# LED.net
KiCad netlist of a schematic drawn in Altium Designer
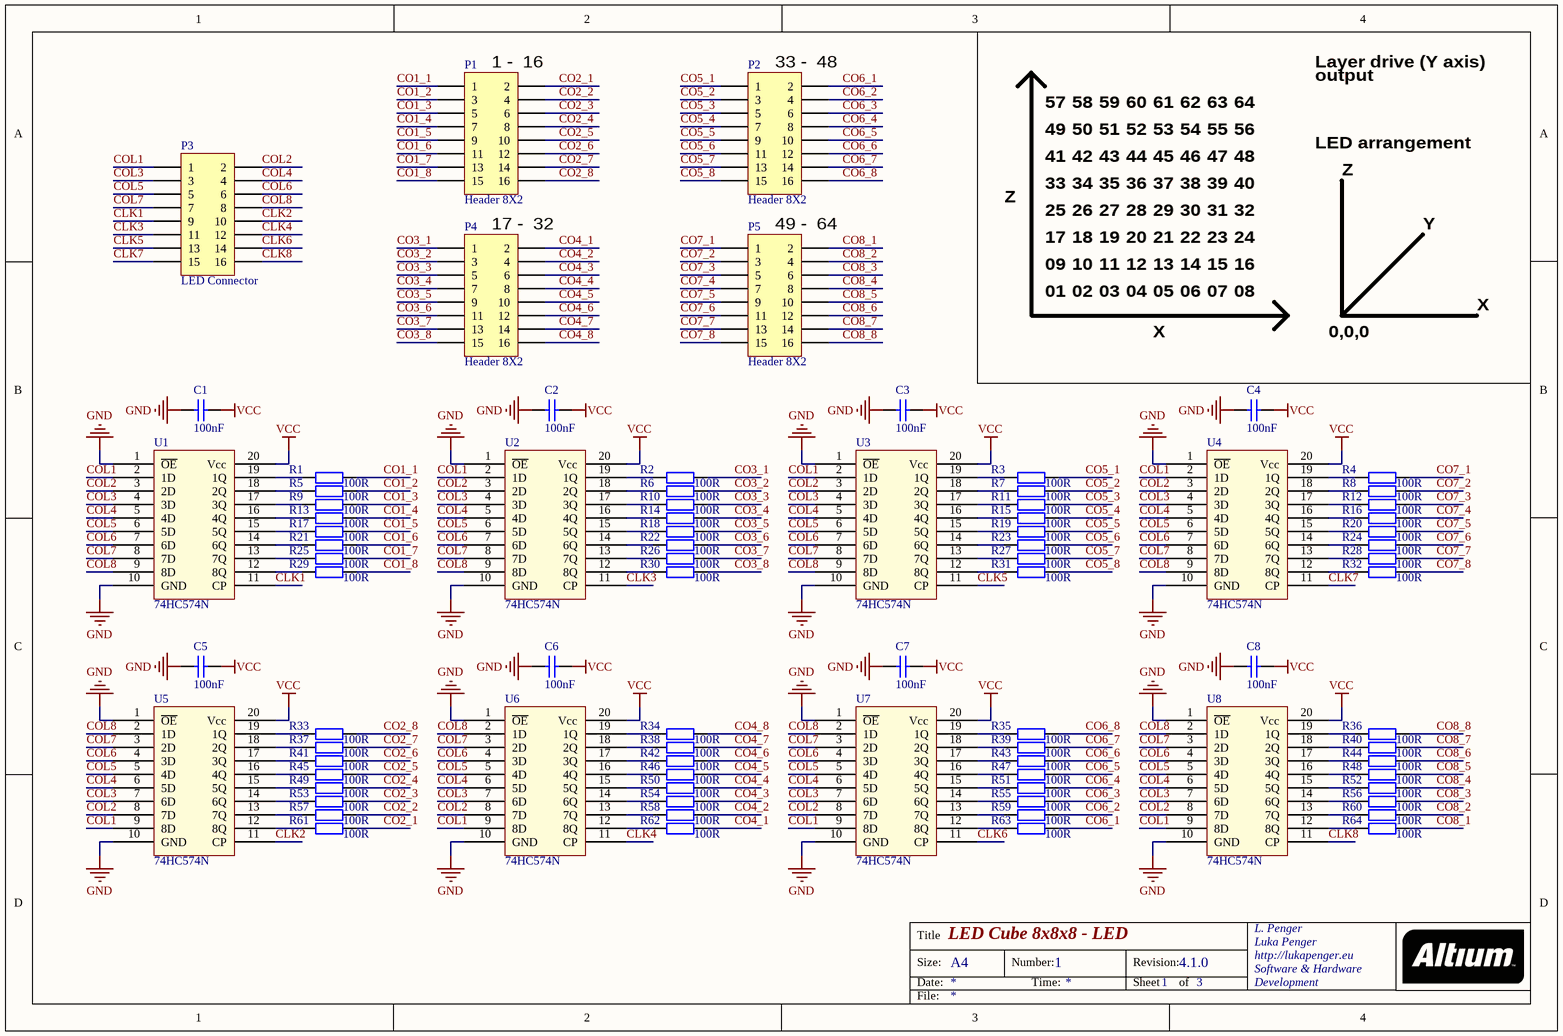
[diagram p0: LED.SchDoc]

(export (version "E")
  (design (tool "Eeschema 10.0.6"))
  (components
    (comp (ref "C1")
      (value "100nF")
      (footprint "1608[0603]")
      (description "Capacitor")
      (fields (field (name "PUBLISHER") "Altium Limited"))
      (libsource (lib "Miscellaneous Devices") (part "Cap"))
    )
    (comp (ref "C2")
      (value "100nF")
      (footprint "1608[0603]")
      (description "Capacitor")
      (fields (field (name "PUBLISHER") "Altium Limited"))
      (libsource (lib "Miscellaneous Devices") (part "Cap"))
    )
    (comp (ref "C3")
      (value "100nF")
      (footprint "1608[0603]")
      (description "Capacitor")
      (fields (field (name "PUBLISHER") "Altium Limited"))
      (libsource (lib "Miscellaneous Devices") (part "Cap"))
    )
    (comp (ref "C4")
      (value "100nF")
      (footprint "1608[0603]")
      (description "Capacitor")
      (fields (field (name "PUBLISHER") "Altium Limited"))
      (libsource (lib "Miscellaneous Devices") (part "Cap"))
    )
    (comp (ref "C5")
      (value "100nF")
      (footprint "1608[0603]")
      (description "Capacitor")
      (fields (field (name "PUBLISHER") "Altium Limited"))
      (libsource (lib "Miscellaneous Devices") (part "Cap"))
    )
    (comp (ref "C6")
      (value "100nF")
      (footprint "1608[0603]")
      (description "Capacitor")
      (fields (field (name "PUBLISHER") "Altium Limited"))
      (libsource (lib "Miscellaneous Devices") (part "Cap"))
    )
    (comp (ref "C7")
      (value "100nF")
      (footprint "1608[0603]")
      (description "Capacitor")
      (fields (field (name "PUBLISHER") "Altium Limited"))
      (libsource (lib "Miscellaneous Devices") (part "Cap"))
    )
    (comp (ref "C8")
      (value "100nF")
      (footprint "1608[0603]")
      (description "Capacitor")
      (fields (field (name "PUBLISHER") "Altium Limited"))
      (libsource (lib "Miscellaneous Devices") (part "Cap"))
    )
    (comp (ref "P1")
      (value "Header 8X2")
      (footprint "IDC-2x8")
      (description "Header, 8-Pin, Dual row")
      (fields (field (name "PUBLISHER") "Altium Limited"))
      (libsource (lib "Miscellaneous Connectors") (part "Header 8X2"))
    )
    (comp (ref "P2")
      (value "Header 8X2")
      (footprint "IDC-2x8")
      (description "Header, 8-Pin, Dual row")
      (fields (field (name "PUBLISHER") "Altium Limited"))
      (libsource (lib "Miscellaneous Connectors") (part "Header 8X2"))
    )
    (comp (ref "P3")
      (value "LED Connector")
      (footprint "IDC-2x8")
      (description "Header, 8-Pin, Dual row")
      (fields (field (name "PUBLISHER") "Altium Limited"))
      (libsource (lib "Miscellaneous Connectors") (part "Header 8X2"))
    )
    (comp (ref "P4")
      (value "Header 8X2")
      (footprint "IDC-2x8")
      (description "Header, 8-Pin, Dual row")
      (fields (field (name "PUBLISHER") "Altium Limited"))
      (libsource (lib "Miscellaneous Connectors") (part "Header 8X2"))
    )
    (comp (ref "P5")
      (value "Header 8X2")
      (footprint "IDC-2x8")
      (description "Header, 8-Pin, Dual row")
      (fields (field (name "PUBLISHER") "Altium Limited"))
      (libsource (lib "Miscellaneous Connectors") (part "Header 8X2"))
    )
    (comp (ref "R1")
      (value "100R")
      (footprint "C1206")
      (description "Resistor")
      (fields (field (name "PUBLISHER") "Altium Limited"))
      (libsource (lib "Miscellaneous Devices") (part "Res2"))
    )
    (comp (ref "R2")
      (value "100R")
      (footprint "C1206")
      (description "Resistor")
      (fields (field (name "PUBLISHER") "Altium Limited"))
      (libsource (lib "Miscellaneous Devices") (part "Res2"))
    )
    (comp (ref "R3")
      (value "100R")
      (footprint "C1206")
      (description "Resistor")
      (fields (field (name "PUBLISHER") "Altium Limited"))
      (libsource (lib "Miscellaneous Devices") (part "Res2"))
    )
    (comp (ref "R4")
      (value "100R")
      (footprint "C1206")
      (description "Resistor")
      (fields (field (name "PUBLISHER") "Altium Limited"))
      (libsource (lib "Miscellaneous Devices") (part "Res2"))
    )
    (comp (ref "R5")
      (value "100R")
      (footprint "C1206")
      (description "Resistor")
      (fields (field (name "PUBLISHER") "Altium Limited"))
      (libsource (lib "Miscellaneous Devices") (part "Res2"))
    )
    (comp (ref "R6")
      (value "100R")
      (footprint "C1206")
      (description "Resistor")
      (fields (field (name "PUBLISHER") "Altium Limited"))
      (libsource (lib "Miscellaneous Devices") (part "Res2"))
    )
    (comp (ref "R7")
      (value "100R")
      (footprint "C1206")
      (description "Resistor")
      (fields (field (name "PUBLISHER") "Altium Limited"))
      (libsource (lib "Miscellaneous Devices") (part "Res2"))
    )
    (comp (ref "R8")
      (value "100R")
      (footprint "C1206")
      (description "Resistor")
      (fields (field (name "PUBLISHER") "Altium Limited"))
      (libsource (lib "Miscellaneous Devices") (part "Res2"))
    )
    (comp (ref "R9")
      (value "100R")
      (footprint "C1206")
      (description "Resistor")
      (fields (field (name "PUBLISHER") "Altium Limited"))
      (libsource (lib "Miscellaneous Devices") (part "Res2"))
    )
    (comp (ref "R10")
      (value "100R")
      (footprint "C1206")
      (description "Resistor")
      (fields (field (name "PUBLISHER") "Altium Limited"))
      (libsource (lib "Miscellaneous Devices") (part "Res2"))
    )
    (comp (ref "R11")
      (value "100R")
      (footprint "C1206")
      (description "Resistor")
      (fields (field (name "PUBLISHER") "Altium Limited"))
      (libsource (lib "Miscellaneous Devices") (part "Res2"))
    )
    (comp (ref "R12")
      (value "100R")
      (footprint "C1206")
      (description "Resistor")
      (fields (field (name "PUBLISHER") "Altium Limited"))
      (libsource (lib "Miscellaneous Devices") (part "Res2"))
    )
    (comp (ref "R13")
      (value "100R")
      (footprint "C1206")
      (description "Resistor")
      (fields (field (name "PUBLISHER") "Altium Limited"))
      (libsource (lib "Miscellaneous Devices") (part "Res2"))
    )
    (comp (ref "R14")
      (value "100R")
      (footprint "C1206")
      (description "Resistor")
      (fields (field (name "PUBLISHER") "Altium Limited"))
      (libsource (lib "Miscellaneous Devices") (part "Res2"))
    )
    (comp (ref "R15")
      (value "100R")
      (footprint "C1206")
      (description "Resistor")
      (fields (field (name "PUBLISHER") "Altium Limited"))
      (libsource (lib "Miscellaneous Devices") (part "Res2"))
    )
    (comp (ref "R16")
      (value "100R")
      (footprint "C1206")
      (description "Resistor")
      (fields (field (name "PUBLISHER") "Altium Limited"))
      (libsource (lib "Miscellaneous Devices") (part "Res2"))
    )
    (comp (ref "R17")
      (value "100R")
      (footprint "C1206")
      (description "Resistor")
      (fields (field (name "PUBLISHER") "Altium Limited"))
      (libsource (lib "Miscellaneous Devices") (part "Res2"))
    )
    (comp (ref "R18")
      (value "100R")
      (footprint "C1206")
      (description "Resistor")
      (fields (field (name "PUBLISHER") "Altium Limited"))
      (libsource (lib "Miscellaneous Devices") (part "Res2"))
    )
    (comp (ref "R19")
      (value "100R")
      (footprint "C1206")
      (description "Resistor")
      (fields (field (name "PUBLISHER") "Altium Limited"))
      (libsource (lib "Miscellaneous Devices") (part "Res2"))
    )
    (comp (ref "R20")
      (value "100R")
      (footprint "C1206")
      (description "Resistor")
      (fields (field (name "PUBLISHER") "Altium Limited"))
      (libsource (lib "Miscellaneous Devices") (part "Res2"))
    )
    (comp (ref "R21")
      (value "100R")
      (footprint "C1206")
      (description "Resistor")
      (fields (field (name "PUBLISHER") "Altium Limited"))
      (libsource (lib "Miscellaneous Devices") (part "Res2"))
    )
    (comp (ref "R22")
      (value "100R")
      (footprint "C1206")
      (description "Resistor")
      (fields (field (name "PUBLISHER") "Altium Limited"))
      (libsource (lib "Miscellaneous Devices") (part "Res2"))
    )
    (comp (ref "R23")
      (value "100R")
      (footprint "C1206")
      (description "Resistor")
      (fields (field (name "PUBLISHER") "Altium Limited"))
      (libsource (lib "Miscellaneous Devices") (part "Res2"))
    )
    (comp (ref "R24")
      (value "100R")
      (footprint "C1206")
      (description "Resistor")
      (fields (field (name "PUBLISHER") "Altium Limited"))
      (libsource (lib "Miscellaneous Devices") (part "Res2"))
    )
    (comp (ref "R25")
      (value "100R")
      (footprint "C1206")
      (description "Resistor")
      (fields (field (name "PUBLISHER") "Altium Limited"))
      (libsource (lib "Miscellaneous Devices") (part "Res2"))
    )
    (comp (ref "R26")
      (value "100R")
      (footprint "C1206")
      (description "Resistor")
      (fields (field (name "PUBLISHER") "Altium Limited"))
      (libsource (lib "Miscellaneous Devices") (part "Res2"))
    )
    (comp (ref "R27")
      (value "100R")
      (footprint "C1206")
      (description "Resistor")
      (fields (field (name "PUBLISHER") "Altium Limited"))
      (libsource (lib "Miscellaneous Devices") (part "Res2"))
    )
    (comp (ref "R28")
      (value "100R")
      (footprint "C1206")
      (description "Resistor")
      (fields (field (name "PUBLISHER") "Altium Limited"))
      (libsource (lib "Miscellaneous Devices") (part "Res2"))
    )
    (comp (ref "R29")
      (value "100R")
      (footprint "C1206")
      (description "Resistor")
      (fields (field (name "PUBLISHER") "Altium Limited"))
      (libsource (lib "Miscellaneous Devices") (part "Res2"))
    )
    (comp (ref "R30")
      (value "100R")
      (footprint "C1206")
      (description "Resistor")
      (fields (field (name "PUBLISHER") "Altium Limited"))
      (libsource (lib "Miscellaneous Devices") (part "Res2"))
    )
    (comp (ref "R31")
      (value "100R")
      (footprint "C1206")
      (description "Resistor")
      (fields (field (name "PUBLISHER") "Altium Limited"))
      (libsource (lib "Miscellaneous Devices") (part "Res2"))
    )
    (comp (ref "R32")
      (value "100R")
      (footprint "C1206")
      (description "Resistor")
      (fields (field (name "PUBLISHER") "Altium Limited"))
      (libsource (lib "Miscellaneous Devices") (part "Res2"))
    )
    (comp (ref "R33")
      (value "100R")
      (footprint "C1206")
      (description "Resistor")
      (fields (field (name "PUBLISHER") "Altium Limited"))
      (libsource (lib "Miscellaneous Devices") (part "Res2"))
    )
    (comp (ref "R34")
      (value "100R")
      (footprint "C1206")
      (description "Resistor")
      (fields (field (name "PUBLISHER") "Altium Limited"))
      (libsource (lib "Miscellaneous Devices") (part "Res2"))
    )
    (comp (ref "R35")
      (value "100R")
      (footprint "C1206")
      (description "Resistor")
      (fields (field (name "PUBLISHER") "Altium Limited"))
      (libsource (lib "Miscellaneous Devices") (part "Res2"))
    )
    (comp (ref "R36")
      (value "100R")
      (footprint "C1206")
      (description "Resistor")
      (fields (field (name "PUBLISHER") "Altium Limited"))
      (libsource (lib "Miscellaneous Devices") (part "Res2"))
    )
    (comp (ref "R37")
      (value "100R")
      (footprint "C1206")
      (description "Resistor")
      (fields (field (name "PUBLISHER") "Altium Limited"))
      (libsource (lib "Miscellaneous Devices") (part "Res2"))
    )
    (comp (ref "R38")
      (value "100R")
      (footprint "C1206")
      (description "Resistor")
      (fields (field (name "PUBLISHER") "Altium Limited"))
      (libsource (lib "Miscellaneous Devices") (part "Res2"))
    )
    (comp (ref "R39")
      (value "100R")
      (footprint "C1206")
      (description "Resistor")
      (fields (field (name "PUBLISHER") "Altium Limited"))
      (libsource (lib "Miscellaneous Devices") (part "Res2"))
    )
    (comp (ref "R40")
      (value "100R")
      (footprint "C1206")
      (description "Resistor")
      (fields (field (name "PUBLISHER") "Altium Limited"))
      (libsource (lib "Miscellaneous Devices") (part "Res2"))
    )
    (comp (ref "R41")
      (value "100R")
      (footprint "C1206")
      (description "Resistor")
      (fields (field (name "PUBLISHER") "Altium Limited"))
      (libsource (lib "Miscellaneous Devices") (part "Res2"))
    )
    (comp (ref "R42")
      (value "100R")
      (footprint "C1206")
      (description "Resistor")
      (fields (field (name "PUBLISHER") "Altium Limited"))
      (libsource (lib "Miscellaneous Devices") (part "Res2"))
    )
    (comp (ref "R43")
      (value "100R")
      (footprint "C1206")
      (description "Resistor")
      (fields (field (name "PUBLISHER") "Altium Limited"))
      (libsource (lib "Miscellaneous Devices") (part "Res2"))
    )
    (comp (ref "R44")
      (value "100R")
      (footprint "C1206")
      (description "Resistor")
      (fields (field (name "PUBLISHER") "Altium Limited"))
      (libsource (lib "Miscellaneous Devices") (part "Res2"))
    )
    (comp (ref "R45")
      (value "100R")
      (footprint "C1206")
      (description "Resistor")
      (fields (field (name "PUBLISHER") "Altium Limited"))
      (libsource (lib "Miscellaneous Devices") (part "Res2"))
    )
    (comp (ref "R46")
      (value "100R")
      (footprint "C1206")
      (description "Resistor")
      (fields (field (name "PUBLISHER") "Altium Limited"))
      (libsource (lib "Miscellaneous Devices") (part "Res2"))
    )
    (comp (ref "R47")
      (value "100R")
      (footprint "C1206")
      (description "Resistor")
      (fields (field (name "PUBLISHER") "Altium Limited"))
      (libsource (lib "Miscellaneous Devices") (part "Res2"))
    )
    (comp (ref "R48")
      (value "100R")
      (footprint "C1206")
      (description "Resistor")
      (fields (field (name "PUBLISHER") "Altium Limited"))
      (libsource (lib "Miscellaneous Devices") (part "Res2"))
    )
    (comp (ref "R49")
      (value "100R")
      (footprint "C1206")
      (description "Resistor")
      (fields (field (name "PUBLISHER") "Altium Limited"))
      (libsource (lib "Miscellaneous Devices") (part "Res2"))
    )
    (comp (ref "R50")
      (value "100R")
      (footprint "C1206")
      (description "Resistor")
      (fields (field (name "PUBLISHER") "Altium Limited"))
      (libsource (lib "Miscellaneous Devices") (part "Res2"))
    )
    (comp (ref "R51")
      (value "100R")
      (footprint "C1206")
      (description "Resistor")
      (fields (field (name "PUBLISHER") "Altium Limited"))
      (libsource (lib "Miscellaneous Devices") (part "Res2"))
    )
    (comp (ref "R52")
      (value "100R")
      (footprint "C1206")
      (description "Resistor")
      (fields (field (name "PUBLISHER") "Altium Limited"))
      (libsource (lib "Miscellaneous Devices") (part "Res2"))
    )
    (comp (ref "R53")
      (value "100R")
      (footprint "C1206")
      (description "Resistor")
      (fields (field (name "PUBLISHER") "Altium Limited"))
      (libsource (lib "Miscellaneous Devices") (part "Res2"))
    )
    (comp (ref "R54")
      (value "100R")
      (footprint "C1206")
      (description "Resistor")
      (fields (field (name "PUBLISHER") "Altium Limited"))
      (libsource (lib "Miscellaneous Devices") (part "Res2"))
    )
    (comp (ref "R55")
      (value "100R")
      (footprint "C1206")
      (description "Resistor")
      (fields (field (name "PUBLISHER") "Altium Limited"))
      (libsource (lib "Miscellaneous Devices") (part "Res2"))
    )
    (comp (ref "R56")
      (value "100R")
      (footprint "C1206")
      (description "Resistor")
      (fields (field (name "PUBLISHER") "Altium Limited"))
      (libsource (lib "Miscellaneous Devices") (part "Res2"))
    )
    (comp (ref "R57")
      (value "100R")
      (footprint "C1206")
      (description "Resistor")
      (fields (field (name "PUBLISHER") "Altium Limited"))
      (libsource (lib "Miscellaneous Devices") (part "Res2"))
    )
    (comp (ref "R58")
      (value "100R")
      (footprint "C1206")
      (description "Resistor")
      (fields (field (name "PUBLISHER") "Altium Limited"))
      (libsource (lib "Miscellaneous Devices") (part "Res2"))
    )
    (comp (ref "R59")
      (value "100R")
      (footprint "C1206")
      (description "Resistor")
      (fields (field (name "PUBLISHER") "Altium Limited"))
      (libsource (lib "Miscellaneous Devices") (part "Res2"))
    )
    (comp (ref "R60")
      (value "100R")
      (footprint "C1206")
      (description "Resistor")
      (fields (field (name "PUBLISHER") "Altium Limited"))
      (libsource (lib "Miscellaneous Devices") (part "Res2"))
    )
    (comp (ref "R61")
      (value "100R")
      (footprint "C1206")
      (description "Resistor")
      (fields (field (name "PUBLISHER") "Altium Limited"))
      (libsource (lib "Miscellaneous Devices") (part "Res2"))
    )
    (comp (ref "R62")
      (value "100R")
      (footprint "C1206")
      (description "Resistor")
      (fields (field (name "PUBLISHER") "Altium Limited"))
      (libsource (lib "Miscellaneous Devices") (part "Res2"))
    )
    (comp (ref "R63")
      (value "100R")
      (footprint "C1206")
      (description "Resistor")
      (fields (field (name "PUBLISHER") "Altium Limited"))
      (libsource (lib "Miscellaneous Devices") (part "Res2"))
    )
    (comp (ref "R64")
      (value "100R")
      (footprint "C1206")
      (description "Resistor")
      (fields (field (name "PUBLISHER") "Altium Limited"))
      (libsource (lib "Miscellaneous Devices") (part "Res2"))
    )
    (comp (ref "U1")
      (value "74HC574N")
      (footprint "DIP20")
      (description "D Flip Flops")
      (libsource (lib "LukaLIBRARY") (part "74HCT574"))
    )
    (comp (ref "U2")
      (value "74HC574N")
      (footprint "DIP20")
      (description "D Flip Flops")
      (libsource (lib "LukaLIBRARY") (part "74HCT574"))
    )
    (comp (ref "U3")
      (value "74HC574N")
      (footprint "DIP20")
      (description "D Flip Flops")
      (libsource (lib "LukaLIBRARY") (part "74HCT574"))
    )
    (comp (ref "U4")
      (value "74HC574N")
      (footprint "DIP20")
      (description "D Flip Flops")
      (libsource (lib "LukaLIBRARY") (part "74HCT574"))
    )
    (comp (ref "U5")
      (value "74HC574N")
      (footprint "DIP20")
      (description "D Flip Flops")
      (libsource (lib "LukaLIBRARY") (part "74HCT574"))
    )
    (comp (ref "U6")
      (value "74HC574N")
      (footprint "DIP20")
      (description "D Flip Flops")
      (libsource (lib "LukaLIBRARY") (part "74HCT574"))
    )
    (comp (ref "U7")
      (value "74HC574N")
      (footprint "DIP20")
      (description "D Flip Flops")
      (libsource (lib "LukaLIBRARY") (part "74HCT574"))
    )
    (comp (ref "U8")
      (value "74HC574N")
      (footprint "DIP20")
      (description "D Flip Flops")
      (libsource (lib "LukaLIBRARY") (part "74HCT574"))
    )
  )
  (nets
    (net (code "1") (name "/CLK1") (class "Default")
      (node (ref "P3") (pin "9") (pinfunction "9_9") (pintype "passive"))
      (node (ref "U1") (pin "11") (pinfunction "CP_11") (pintype "passive"))
    )
    (net (code "2") (name "/CLK2") (class "Default")
      (node (ref "P3") (pin "10") (pinfunction "10_10") (pintype "passive"))
      (node (ref "U5") (pin "11") (pinfunction "CP_11") (pintype "passive"))
    )
    (net (code "3") (name "/CLK3") (class "Default")
      (node (ref "P3") (pin "11") (pinfunction "11_11") (pintype "passive"))
      (node (ref "U2") (pin "11") (pinfunction "CP_11") (pintype "passive"))
    )
    (net (code "4") (name "/CLK4") (class "Default")
      (node (ref "P3") (pin "12") (pinfunction "12_12") (pintype "passive"))
      (node (ref "U6") (pin "11") (pinfunction "CP_11") (pintype "passive"))
    )
    (net (code "5") (name "/CLK5") (class "Default")
      (node (ref "P3") (pin "13") (pinfunction "13_13") (pintype "passive"))
      (node (ref "U3") (pin "11") (pinfunction "CP_11") (pintype "passive"))
    )
    (net (code "6") (name "/CLK6") (class "Default")
      (node (ref "P3") (pin "14") (pinfunction "14_14") (pintype "passive"))
      (node (ref "U7") (pin "11") (pinfunction "CP_11") (pintype "passive"))
    )
    (net (code "7") (name "/CLK7") (class "Default")
      (node (ref "P3") (pin "15") (pinfunction "15_15") (pintype "passive"))
      (node (ref "U4") (pin "11") (pinfunction "CP_11") (pintype "passive"))
    )
    (net (code "8") (name "/CLK8") (class "Default")
      (node (ref "P3") (pin "16") (pinfunction "16_16") (pintype "passive"))
      (node (ref "U8") (pin "11") (pinfunction "CP_11") (pintype "passive"))
    )
    (net (code "9") (name "/CO1_1") (class "Default")
      (node (ref "P1") (pin "1") (pinfunction "1_1") (pintype "passive"))
      (node (ref "R1") (pin "2") (pinfunction "2_2") (pintype "passive"))
    )
    (net (code "10") (name "/CO1_2") (class "Default")
      (node (ref "P1") (pin "3") (pinfunction "3_3") (pintype "passive"))
      (node (ref "R5") (pin "2") (pinfunction "2_2") (pintype "passive"))
    )
    (net (code "11") (name "/CO1_3") (class "Default")
      (node (ref "P1") (pin "5") (pinfunction "5_5") (pintype "passive"))
      (node (ref "R9") (pin "2") (pinfunction "2_2") (pintype "passive"))
    )
    (net (code "12") (name "/CO1_4") (class "Default")
      (node (ref "P1") (pin "7") (pinfunction "7_7") (pintype "passive"))
      (node (ref "R13") (pin "2") (pinfunction "2_2") (pintype "passive"))
    )
    (net (code "13") (name "/CO1_5") (class "Default")
      (node (ref "P1") (pin "9") (pinfunction "9_9") (pintype "passive"))
      (node (ref "R17") (pin "2") (pinfunction "2_2") (pintype "passive"))
    )
    (net (code "14") (name "/CO1_6") (class "Default")
      (node (ref "P1") (pin "11") (pinfunction "11_11") (pintype "passive"))
      (node (ref "R21") (pin "2") (pinfunction "2_2") (pintype "passive"))
    )
    (net (code "15") (name "/CO1_7") (class "Default")
      (node (ref "P1") (pin "13") (pinfunction "13_13") (pintype "passive"))
      (node (ref "R25") (pin "2") (pinfunction "2_2") (pintype "passive"))
    )
    (net (code "16") (name "/CO1_8") (class "Default")
      (node (ref "P1") (pin "15") (pinfunction "15_15") (pintype "passive"))
      (node (ref "R29") (pin "2") (pinfunction "2_2") (pintype "passive"))
    )
    (net (code "17") (name "/CO2_1") (class "Default")
      (node (ref "P1") (pin "2") (pinfunction "2_2") (pintype "passive"))
      (node (ref "R61") (pin "2") (pinfunction "2_2") (pintype "passive"))
    )
    (net (code "18") (name "/CO2_2") (class "Default")
      (node (ref "P1") (pin "4") (pinfunction "4_4") (pintype "passive"))
      (node (ref "R57") (pin "2") (pinfunction "2_2") (pintype "passive"))
    )
    (net (code "19") (name "/CO2_3") (class "Default")
      (node (ref "P1") (pin "6") (pinfunction "6_6") (pintype "passive"))
      (node (ref "R53") (pin "2") (pinfunction "2_2") (pintype "passive"))
    )
    (net (code "20") (name "/CO2_4") (class "Default")
      (node (ref "P1") (pin "8") (pinfunction "8_8") (pintype "passive"))
      (node (ref "R49") (pin "2") (pinfunction "2_2") (pintype "passive"))
    )
    (net (code "21") (name "/CO2_5") (class "Default")
      (node (ref "P1") (pin "10") (pinfunction "10_10") (pintype "passive"))
      (node (ref "R45") (pin "2") (pinfunction "2_2") (pintype "passive"))
    )
    (net (code "22") (name "/CO2_6") (class "Default")
      (node (ref "P1") (pin "12") (pinfunction "12_12") (pintype "passive"))
      (node (ref "R41") (pin "2") (pinfunction "2_2") (pintype "passive"))
    )
    (net (code "23") (name "/CO2_7") (class "Default")
      (node (ref "P1") (pin "14") (pinfunction "14_14") (pintype "passive"))
      (node (ref "R37") (pin "2") (pinfunction "2_2") (pintype "passive"))
    )
    (net (code "24") (name "/CO2_8") (class "Default")
      (node (ref "P1") (pin "16") (pinfunction "16_16") (pintype "passive"))
      (node (ref "R33") (pin "2") (pinfunction "2_2") (pintype "passive"))
    )
    (net (code "25") (name "/CO3_1") (class "Default")
      (node (ref "P4") (pin "1") (pinfunction "1_1") (pintype "passive"))
      (node (ref "R2") (pin "2") (pinfunction "2_2") (pintype "passive"))
    )
    (net (code "26") (name "/CO3_2") (class "Default")
      (node (ref "P4") (pin "3") (pinfunction "3_3") (pintype "passive"))
      (node (ref "R6") (pin "2") (pinfunction "2_2") (pintype "passive"))
    )
    (net (code "27") (name "/CO3_3") (class "Default")
      (node (ref "P4") (pin "5") (pinfunction "5_5") (pintype "passive"))
      (node (ref "R10") (pin "2") (pinfunction "2_2") (pintype "passive"))
    )
    (net (code "28") (name "/CO3_4") (class "Default")
      (node (ref "P4") (pin "7") (pinfunction "7_7") (pintype "passive"))
      (node (ref "R14") (pin "2") (pinfunction "2_2") (pintype "passive"))
    )
    (net (code "29") (name "/CO3_5") (class "Default")
      (node (ref "P4") (pin "9") (pinfunction "9_9") (pintype "passive"))
      (node (ref "R18") (pin "2") (pinfunction "2_2") (pintype "passive"))
    )
    (net (code "30") (name "/CO3_6") (class "Default")
      (node (ref "P4") (pin "11") (pinfunction "11_11") (pintype "passive"))
      (node (ref "R22") (pin "2") (pinfunction "2_2") (pintype "passive"))
    )
    (net (code "31") (name "/CO3_7") (class "Default")
      (node (ref "P4") (pin "13") (pinfunction "13_13") (pintype "passive"))
      (node (ref "R26") (pin "2") (pinfunction "2_2") (pintype "passive"))
    )
    (net (code "32") (name "/CO3_8") (class "Default")
      (node (ref "P4") (pin "15") (pinfunction "15_15") (pintype "passive"))
      (node (ref "R30") (pin "2") (pinfunction "2_2") (pintype "passive"))
    )
    (net (code "33") (name "/CO4_1") (class "Default")
      (node (ref "P4") (pin "2") (pinfunction "2_2") (pintype "passive"))
      (node (ref "R62") (pin "2") (pinfunction "2_2") (pintype "passive"))
    )
    (net (code "34") (name "/CO4_2") (class "Default")
      (node (ref "P4") (pin "4") (pinfunction "4_4") (pintype "passive"))
      (node (ref "R58") (pin "2") (pinfunction "2_2") (pintype "passive"))
    )
    (net (code "35") (name "/CO4_3") (class "Default")
      (node (ref "P4") (pin "6") (pinfunction "6_6") (pintype "passive"))
      (node (ref "R54") (pin "2") (pinfunction "2_2") (pintype "passive"))
    )
    (net (code "36") (name "/CO4_4") (class "Default")
      (node (ref "P4") (pin "8") (pinfunction "8_8") (pintype "passive"))
      (node (ref "R50") (pin "2") (pinfunction "2_2") (pintype "passive"))
    )
    (net (code "37") (name "/CO4_5") (class "Default")
      (node (ref "P4") (pin "10") (pinfunction "10_10") (pintype "passive"))
      (node (ref "R46") (pin "2") (pinfunction "2_2") (pintype "passive"))
    )
    (net (code "38") (name "/CO4_6") (class "Default")
      (node (ref "P4") (pin "12") (pinfunction "12_12") (pintype "passive"))
      (node (ref "R42") (pin "2") (pinfunction "2_2") (pintype "passive"))
    )
    (net (code "39") (name "/CO4_7") (class "Default")
      (node (ref "P4") (pin "14") (pinfunction "14_14") (pintype "passive"))
      (node (ref "R38") (pin "2") (pinfunction "2_2") (pintype "passive"))
    )
    (net (code "40") (name "/CO4_8") (class "Default")
      (node (ref "P4") (pin "16") (pinfunction "16_16") (pintype "passive"))
      (node (ref "R34") (pin "2") (pinfunction "2_2") (pintype "passive"))
    )
    (net (code "41") (name "/CO5_1") (class "Default")
      (node (ref "P2") (pin "1") (pinfunction "1_1") (pintype "passive"))
      (node (ref "R3") (pin "2") (pinfunction "2_2") (pintype "passive"))
    )
    (net (code "42") (name "/CO5_2") (class "Default")
      (node (ref "P2") (pin "3") (pinfunction "3_3") (pintype "passive"))
      (node (ref "R7") (pin "2") (pinfunction "2_2") (pintype "passive"))
    )
    (net (code "43") (name "/CO5_3") (class "Default")
      (node (ref "P2") (pin "5") (pinfunction "5_5") (pintype "passive"))
      (node (ref "R11") (pin "2") (pinfunction "2_2") (pintype "passive"))
    )
    (net (code "44") (name "/CO5_4") (class "Default")
      (node (ref "P2") (pin "7") (pinfunction "7_7") (pintype "passive"))
      (node (ref "R15") (pin "2") (pinfunction "2_2") (pintype "passive"))
    )
    (net (code "45") (name "/CO5_5") (class "Default")
      (node (ref "P2") (pin "9") (pinfunction "9_9") (pintype "passive"))
      (node (ref "R19") (pin "2") (pinfunction "2_2") (pintype "passive"))
    )
    (net (code "46") (name "/CO5_6") (class "Default")
      (node (ref "P2") (pin "11") (pinfunction "11_11") (pintype "passive"))
      (node (ref "R23") (pin "2") (pinfunction "2_2") (pintype "passive"))
    )
    (net (code "47") (name "/CO5_7") (class "Default")
      (node (ref "P2") (pin "13") (pinfunction "13_13") (pintype "passive"))
      (node (ref "R27") (pin "2") (pinfunction "2_2") (pintype "passive"))
    )
    (net (code "48") (name "/CO5_8") (class "Default")
      (node (ref "P2") (pin "15") (pinfunction "15_15") (pintype "passive"))
      (node (ref "R31") (pin "2") (pinfunction "2_2") (pintype "passive"))
    )
    (net (code "49") (name "/CO6_1") (class "Default")
      (node (ref "P2") (pin "2") (pinfunction "2_2") (pintype "passive"))
      (node (ref "R63") (pin "2") (pinfunction "2_2") (pintype "passive"))
    )
    (net (code "50") (name "/CO6_2") (class "Default")
      (node (ref "P2") (pin "4") (pinfunction "4_4") (pintype "passive"))
      (node (ref "R59") (pin "2") (pinfunction "2_2") (pintype "passive"))
    )
    (net (code "51") (name "/CO6_3") (class "Default")
      (node (ref "P2") (pin "6") (pinfunction "6_6") (pintype "passive"))
      (node (ref "R55") (pin "2") (pinfunction "2_2") (pintype "passive"))
    )
    (net (code "52") (name "/CO6_4") (class "Default")
      (node (ref "P2") (pin "8") (pinfunction "8_8") (pintype "passive"))
      (node (ref "R51") (pin "2") (pinfunction "2_2") (pintype "passive"))
    )
    (net (code "53") (name "/CO6_5") (class "Default")
      (node (ref "P2") (pin "10") (pinfunction "10_10") (pintype "passive"))
      (node (ref "R47") (pin "2") (pinfunction "2_2") (pintype "passive"))
    )
    (net (code "54") (name "/CO6_6") (class "Default")
      (node (ref "P2") (pin "12") (pinfunction "12_12") (pintype "passive"))
      (node (ref "R43") (pin "2") (pinfunction "2_2") (pintype "passive"))
    )
    (net (code "55") (name "/CO6_7") (class "Default")
      (node (ref "P2") (pin "14") (pinfunction "14_14") (pintype "passive"))
      (node (ref "R39") (pin "2") (pinfunction "2_2") (pintype "passive"))
    )
    (net (code "56") (name "/CO6_8") (class "Default")
      (node (ref "P2") (pin "16") (pinfunction "16_16") (pintype "passive"))
      (node (ref "R35") (pin "2") (pinfunction "2_2") (pintype "passive"))
    )
    (net (code "57") (name "/CO7_1") (class "Default")
      (node (ref "P5") (pin "1") (pinfunction "1_1") (pintype "passive"))
      (node (ref "R4") (pin "2") (pinfunction "2_2") (pintype "passive"))
    )
    (net (code "58") (name "/CO7_2") (class "Default")
      (node (ref "P5") (pin "3") (pinfunction "3_3") (pintype "passive"))
      (node (ref "R8") (pin "2") (pinfunction "2_2") (pintype "passive"))
    )
    (net (code "59") (name "/CO7_3") (class "Default")
      (node (ref "P5") (pin "5") (pinfunction "5_5") (pintype "passive"))
      (node (ref "R12") (pin "2") (pinfunction "2_2") (pintype "passive"))
    )
    (net (code "60") (name "/CO7_4") (class "Default")
      (node (ref "P5") (pin "7") (pinfunction "7_7") (pintype "passive"))
      (node (ref "R16") (pin "2") (pinfunction "2_2") (pintype "passive"))
    )
    (net (code "61") (name "/CO7_5") (class "Default")
      (node (ref "P5") (pin "9") (pinfunction "9_9") (pintype "passive"))
      (node (ref "R20") (pin "2") (pinfunction "2_2") (pintype "passive"))
    )
    (net (code "62") (name "/CO7_6") (class "Default")
      (node (ref "P5") (pin "11") (pinfunction "11_11") (pintype "passive"))
      (node (ref "R24") (pin "2") (pinfunction "2_2") (pintype "passive"))
    )
    (net (code "63") (name "/CO7_7") (class "Default")
      (node (ref "P5") (pin "13") (pinfunction "13_13") (pintype "passive"))
      (node (ref "R28") (pin "2") (pinfunction "2_2") (pintype "passive"))
    )
    (net (code "64") (name "/CO7_8") (class "Default")
      (node (ref "P5") (pin "15") (pinfunction "15_15") (pintype "passive"))
      (node (ref "R32") (pin "2") (pinfunction "2_2") (pintype "passive"))
    )
    (net (code "65") (name "/CO8_1") (class "Default")
      (node (ref "P5") (pin "2") (pinfunction "2_2") (pintype "passive"))
      (node (ref "R64") (pin "2") (pinfunction "2_2") (pintype "passive"))
    )
    (net (code "66") (name "/CO8_2") (class "Default")
      (node (ref "P5") (pin "4") (pinfunction "4_4") (pintype "passive"))
      (node (ref "R60") (pin "2") (pinfunction "2_2") (pintype "passive"))
    )
    (net (code "67") (name "/CO8_3") (class "Default")
      (node (ref "P5") (pin "6") (pinfunction "6_6") (pintype "passive"))
      (node (ref "R56") (pin "2") (pinfunction "2_2") (pintype "passive"))
    )
    (net (code "68") (name "/CO8_4") (class "Default")
      (node (ref "P5") (pin "8") (pinfunction "8_8") (pintype "passive"))
      (node (ref "R52") (pin "2") (pinfunction "2_2") (pintype "passive"))
    )
    (net (code "69") (name "/CO8_5") (class "Default")
      (node (ref "P5") (pin "10") (pinfunction "10_10") (pintype "passive"))
      (node (ref "R48") (pin "2") (pinfunction "2_2") (pintype "passive"))
    )
    (net (code "70") (name "/CO8_6") (class "Default")
      (node (ref "P5") (pin "12") (pinfunction "12_12") (pintype "passive"))
      (node (ref "R44") (pin "2") (pinfunction "2_2") (pintype "passive"))
    )
    (net (code "71") (name "/CO8_7") (class "Default")
      (node (ref "P5") (pin "14") (pinfunction "14_14") (pintype "passive"))
      (node (ref "R40") (pin "2") (pinfunction "2_2") (pintype "passive"))
    )
    (net (code "72") (name "/CO8_8") (class "Default")
      (node (ref "P5") (pin "16") (pinfunction "16_16") (pintype "passive"))
      (node (ref "R36") (pin "2") (pinfunction "2_2") (pintype "passive"))
    )
    (net (code "73") (name "/COL1") (class "Default")
      (node (ref "P3") (pin "1") (pinfunction "1_1") (pintype "passive"))
      (node (ref "U1") (pin "2") (pinfunction "1D_2") (pintype "passive"))
      (node (ref "U2") (pin "2") (pinfunction "1D_2") (pintype "passive"))
      (node (ref "U3") (pin "2") (pinfunction "1D_2") (pintype "passive"))
      (node (ref "U4") (pin "2") (pinfunction "1D_2") (pintype "passive"))
      (node (ref "U5") (pin "9") (pinfunction "8D_9") (pintype "passive"))
      (node (ref "U6") (pin "9") (pinfunction "8D_9") (pintype "passive"))
      (node (ref "U7") (pin "9") (pinfunction "8D_9") (pintype "passive"))
      (node (ref "U8") (pin "9") (pinfunction "8D_9") (pintype "passive"))
    )
    (net (code "74") (name "/COL2") (class "Default")
      (node (ref "P3") (pin "2") (pinfunction "2_2") (pintype "passive"))
      (node (ref "U1") (pin "3") (pinfunction "2D_3") (pintype "passive"))
      (node (ref "U2") (pin "3") (pinfunction "2D_3") (pintype "passive"))
      (node (ref "U3") (pin "3") (pinfunction "2D_3") (pintype "passive"))
      (node (ref "U4") (pin "3") (pinfunction "2D_3") (pintype "passive"))
      (node (ref "U5") (pin "8") (pinfunction "7D_8") (pintype "passive"))
      (node (ref "U6") (pin "8") (pinfunction "7D_8") (pintype "passive"))
      (node (ref "U7") (pin "8") (pinfunction "7D_8") (pintype "passive"))
      (node (ref "U8") (pin "8") (pinfunction "7D_8") (pintype "passive"))
    )
    (net (code "75") (name "/COL3") (class "Default")
      (node (ref "P3") (pin "3") (pinfunction "3_3") (pintype "passive"))
      (node (ref "U1") (pin "4") (pinfunction "3D_4") (pintype "passive"))
      (node (ref "U2") (pin "4") (pinfunction "3D_4") (pintype "passive"))
      (node (ref "U3") (pin "4") (pinfunction "3D_4") (pintype "passive"))
      (node (ref "U4") (pin "4") (pinfunction "3D_4") (pintype "passive"))
      (node (ref "U5") (pin "7") (pinfunction "6D_7") (pintype "passive"))
      (node (ref "U6") (pin "7") (pinfunction "6D_7") (pintype "passive"))
      (node (ref "U7") (pin "7") (pinfunction "6D_7") (pintype "passive"))
      (node (ref "U8") (pin "7") (pinfunction "6D_7") (pintype "passive"))
    )
    (net (code "76") (name "/COL4") (class "Default")
      (node (ref "P3") (pin "4") (pinfunction "4_4") (pintype "passive"))
      (node (ref "U1") (pin "5") (pinfunction "4D_5") (pintype "passive"))
      (node (ref "U2") (pin "5") (pinfunction "4D_5") (pintype "passive"))
      (node (ref "U3") (pin "5") (pinfunction "4D_5") (pintype "passive"))
      (node (ref "U4") (pin "5") (pinfunction "4D_5") (pintype "passive"))
      (node (ref "U5") (pin "6") (pinfunction "5D_6") (pintype "passive"))
      (node (ref "U6") (pin "6") (pinfunction "5D_6") (pintype "passive"))
      (node (ref "U7") (pin "6") (pinfunction "5D_6") (pintype "passive"))
      (node (ref "U8") (pin "6") (pinfunction "5D_6") (pintype "passive"))
    )
    (net (code "77") (name "/COL5") (class "Default")
      (node (ref "P3") (pin "5") (pinfunction "5_5") (pintype "passive"))
      (node (ref "U1") (pin "6") (pinfunction "5D_6") (pintype "passive"))
      (node (ref "U2") (pin "6") (pinfunction "5D_6") (pintype "passive"))
      (node (ref "U3") (pin "6") (pinfunction "5D_6") (pintype "passive"))
      (node (ref "U4") (pin "6") (pinfunction "5D_6") (pintype "passive"))
      (node (ref "U5") (pin "5") (pinfunction "4D_5") (pintype "passive"))
      (node (ref "U6") (pin "5") (pinfunction "4D_5") (pintype "passive"))
      (node (ref "U7") (pin "5") (pinfunction "4D_5") (pintype "passive"))
      (node (ref "U8") (pin "5") (pinfunction "4D_5") (pintype "passive"))
    )
    (net (code "78") (name "/COL6") (class "Default")
      (node (ref "P3") (pin "6") (pinfunction "6_6") (pintype "passive"))
      (node (ref "U1") (pin "7") (pinfunction "6D_7") (pintype "passive"))
      (node (ref "U2") (pin "7") (pinfunction "6D_7") (pintype "passive"))
      (node (ref "U3") (pin "7") (pinfunction "6D_7") (pintype "passive"))
      (node (ref "U4") (pin "7") (pinfunction "6D_7") (pintype "passive"))
      (node (ref "U5") (pin "4") (pinfunction "3D_4") (pintype "passive"))
      (node (ref "U6") (pin "4") (pinfunction "3D_4") (pintype "passive"))
      (node (ref "U7") (pin "4") (pinfunction "3D_4") (pintype "passive"))
      (node (ref "U8") (pin "4") (pinfunction "3D_4") (pintype "passive"))
    )
    (net (code "79") (name "/COL7") (class "Default")
      (node (ref "P3") (pin "7") (pinfunction "7_7") (pintype "passive"))
      (node (ref "U1") (pin "8") (pinfunction "7D_8") (pintype "passive"))
      (node (ref "U2") (pin "8") (pinfunction "7D_8") (pintype "passive"))
      (node (ref "U3") (pin "8") (pinfunction "7D_8") (pintype "passive"))
      (node (ref "U4") (pin "8") (pinfunction "7D_8") (pintype "passive"))
      (node (ref "U5") (pin "3") (pinfunction "2D_3") (pintype "passive"))
      (node (ref "U6") (pin "3") (pinfunction "2D_3") (pintype "passive"))
      (node (ref "U7") (pin "3") (pinfunction "2D_3") (pintype "passive"))
      (node (ref "U8") (pin "3") (pinfunction "2D_3") (pintype "passive"))
    )
    (net (code "80") (name "/COL8") (class "Default")
      (node (ref "P3") (pin "8") (pinfunction "8_8") (pintype "passive"))
      (node (ref "U1") (pin "9") (pinfunction "8D_9") (pintype "passive"))
      (node (ref "U2") (pin "9") (pinfunction "8D_9") (pintype "passive"))
      (node (ref "U3") (pin "9") (pinfunction "8D_9") (pintype "passive"))
      (node (ref "U4") (pin "9") (pinfunction "8D_9") (pintype "passive"))
      (node (ref "U5") (pin "2") (pinfunction "1D_2") (pintype "passive"))
      (node (ref "U6") (pin "2") (pinfunction "1D_2") (pintype "passive"))
      (node (ref "U7") (pin "2") (pinfunction "1D_2") (pintype "passive"))
      (node (ref "U8") (pin "2") (pinfunction "1D_2") (pintype "passive"))
    )
    (net (code "81") (name "GND") (class "Default")
      (node (ref "C1") (pin "1") (pinfunction "1_1") (pintype "passive"))
      (node (ref "C2") (pin "1") (pinfunction "1_1") (pintype "passive"))
      (node (ref "C3") (pin "1") (pinfunction "1_1") (pintype "passive"))
      (node (ref "C4") (pin "1") (pinfunction "1_1") (pintype "passive"))
      (node (ref "C5") (pin "1") (pinfunction "1_1") (pintype "passive"))
      (node (ref "C6") (pin "1") (pinfunction "1_1") (pintype "passive"))
      (node (ref "C7") (pin "1") (pinfunction "1_1") (pintype "passive"))
      (node (ref "C8") (pin "1") (pinfunction "1_1") (pintype "passive"))
      (node (ref "U1") (pin "1") (pinfunction "~{OE}_1") (pintype "passive"))
      (node (ref "U1") (pin "10") (pinfunction "GND_10") (pintype "passive"))
      (node (ref "U2") (pin "1") (pinfunction "~{OE}_1") (pintype "passive"))
      (node (ref "U2") (pin "10") (pinfunction "GND_10") (pintype "passive"))
      (node (ref "U3") (pin "1") (pinfunction "~{OE}_1") (pintype "passive"))
      (node (ref "U3") (pin "10") (pinfunction "GND_10") (pintype "passive"))
      (node (ref "U4") (pin "1") (pinfunction "~{OE}_1") (pintype "passive"))
      (node (ref "U4") (pin "10") (pinfunction "GND_10") (pintype "passive"))
      (node (ref "U5") (pin "1") (pinfunction "~{OE}_1") (pintype "passive"))
      (node (ref "U5") (pin "10") (pinfunction "GND_10") (pintype "passive"))
      (node (ref "U6") (pin "1") (pinfunction "~{OE}_1") (pintype "passive"))
      (node (ref "U6") (pin "10") (pinfunction "GND_10") (pintype "passive"))
      (node (ref "U7") (pin "1") (pinfunction "~{OE}_1") (pintype "passive"))
      (node (ref "U7") (pin "10") (pinfunction "GND_10") (pintype "passive"))
      (node (ref "U8") (pin "1") (pinfunction "~{OE}_1") (pintype "passive"))
      (node (ref "U8") (pin "10") (pinfunction "GND_10") (pintype "passive"))
    )
    (net (code "82") (name "Net-(U1-1Q)") (class "Default")
      (node (ref "R1") (pin "1") (pinfunction "1_1") (pintype "passive"))
      (node (ref "U1") (pin "19") (pinfunction "1Q_19") (pintype "passive"))
    )
    (net (code "83") (name "Net-(U1-2Q)") (class "Default")
      (node (ref "R5") (pin "1") (pinfunction "1_1") (pintype "passive"))
      (node (ref "U1") (pin "18") (pinfunction "2Q_18") (pintype "passive"))
    )
    (net (code "84") (name "Net-(U1-3Q)") (class "Default")
      (node (ref "R9") (pin "1") (pinfunction "1_1") (pintype "passive"))
      (node (ref "U1") (pin "17") (pinfunction "3Q_17") (pintype "passive"))
    )
    (net (code "85") (name "Net-(U1-4Q)") (class "Default")
      (node (ref "R13") (pin "1") (pinfunction "1_1") (pintype "passive"))
      (node (ref "U1") (pin "16") (pinfunction "4Q_16") (pintype "passive"))
    )
    (net (code "86") (name "Net-(U1-5Q)") (class "Default")
      (node (ref "R17") (pin "1") (pinfunction "1_1") (pintype "passive"))
      (node (ref "U1") (pin "15") (pinfunction "5Q_15") (pintype "passive"))
    )
    (net (code "87") (name "Net-(U1-6Q)") (class "Default")
      (node (ref "R21") (pin "1") (pinfunction "1_1") (pintype "passive"))
      (node (ref "U1") (pin "14") (pinfunction "6Q_14") (pintype "passive"))
    )
    (net (code "88") (name "Net-(U1-7Q)") (class "Default")
      (node (ref "R25") (pin "1") (pinfunction "1_1") (pintype "passive"))
      (node (ref "U1") (pin "13") (pinfunction "7Q_13") (pintype "passive"))
    )
    (net (code "89") (name "Net-(U1-8Q)") (class "Default")
      (node (ref "R29") (pin "1") (pinfunction "1_1") (pintype "passive"))
      (node (ref "U1") (pin "12") (pinfunction "8Q_12") (pintype "passive"))
    )
    (net (code "90") (name "Net-(U2-1Q)") (class "Default")
      (node (ref "R2") (pin "1") (pinfunction "1_1") (pintype "passive"))
      (node (ref "U2") (pin "19") (pinfunction "1Q_19") (pintype "passive"))
    )
    (net (code "91") (name "Net-(U2-2Q)") (class "Default")
      (node (ref "R6") (pin "1") (pinfunction "1_1") (pintype "passive"))
      (node (ref "U2") (pin "18") (pinfunction "2Q_18") (pintype "passive"))
    )
    (net (code "92") (name "Net-(U2-3Q)") (class "Default")
      (node (ref "R10") (pin "1") (pinfunction "1_1") (pintype "passive"))
      (node (ref "U2") (pin "17") (pinfunction "3Q_17") (pintype "passive"))
    )
    (net (code "93") (name "Net-(U2-4Q)") (class "Default")
      (node (ref "R14") (pin "1") (pinfunction "1_1") (pintype "passive"))
      (node (ref "U2") (pin "16") (pinfunction "4Q_16") (pintype "passive"))
    )
    (net (code "94") (name "Net-(U2-5Q)") (class "Default")
      (node (ref "R18") (pin "1") (pinfunction "1_1") (pintype "passive"))
      (node (ref "U2") (pin "15") (pinfunction "5Q_15") (pintype "passive"))
    )
    (net (code "95") (name "Net-(U2-6Q)") (class "Default")
      (node (ref "R22") (pin "1") (pinfunction "1_1") (pintype "passive"))
      (node (ref "U2") (pin "14") (pinfunction "6Q_14") (pintype "passive"))
    )
    (net (code "96") (name "Net-(U2-7Q)") (class "Default")
      (node (ref "R26") (pin "1") (pinfunction "1_1") (pintype "passive"))
      (node (ref "U2") (pin "13") (pinfunction "7Q_13") (pintype "passive"))
    )
    (net (code "97") (name "Net-(U2-8Q)") (class "Default")
      (node (ref "R30") (pin "1") (pinfunction "1_1") (pintype "passive"))
      (node (ref "U2") (pin "12") (pinfunction "8Q_12") (pintype "passive"))
    )
    (net (code "98") (name "Net-(U3-1Q)") (class "Default")
      (node (ref "R3") (pin "1") (pinfunction "1_1") (pintype "passive"))
      (node (ref "U3") (pin "19") (pinfunction "1Q_19") (pintype "passive"))
    )
    (net (code "99") (name "Net-(U3-2Q)") (class "Default")
      (node (ref "R7") (pin "1") (pinfunction "1_1") (pintype "passive"))
      (node (ref "U3") (pin "18") (pinfunction "2Q_18") (pintype "passive"))
    )
    (net (code "100") (name "Net-(U3-3Q)") (class "Default")
      (node (ref "R11") (pin "1") (pinfunction "1_1") (pintype "passive"))
      (node (ref "U3") (pin "17") (pinfunction "3Q_17") (pintype "passive"))
    )
    (net (code "101") (name "Net-(U3-4Q)") (class "Default")
      (node (ref "R15") (pin "1") (pinfunction "1_1") (pintype "passive"))
      (node (ref "U3") (pin "16") (pinfunction "4Q_16") (pintype "passive"))
    )
    (net (code "102") (name "Net-(U3-5Q)") (class "Default")
      (node (ref "R19") (pin "1") (pinfunction "1_1") (pintype "passive"))
      (node (ref "U3") (pin "15") (pinfunction "5Q_15") (pintype "passive"))
    )
    (net (code "103") (name "Net-(U3-6Q)") (class "Default")
      (node (ref "R23") (pin "1") (pinfunction "1_1") (pintype "passive"))
      (node (ref "U3") (pin "14") (pinfunction "6Q_14") (pintype "passive"))
    )
    (net (code "104") (name "Net-(U3-7Q)") (class "Default")
      (node (ref "R27") (pin "1") (pinfunction "1_1") (pintype "passive"))
      (node (ref "U3") (pin "13") (pinfunction "7Q_13") (pintype "passive"))
    )
    (net (code "105") (name "Net-(U3-8Q)") (class "Default")
      (node (ref "R31") (pin "1") (pinfunction "1_1") (pintype "passive"))
      (node (ref "U3") (pin "12") (pinfunction "8Q_12") (pintype "passive"))
    )
    (net (code "106") (name "Net-(U4-1Q)") (class "Default")
      (node (ref "R4") (pin "1") (pinfunction "1_1") (pintype "passive"))
      (node (ref "U4") (pin "19") (pinfunction "1Q_19") (pintype "passive"))
    )
    (net (code "107") (name "Net-(U4-2Q)") (class "Default")
      (node (ref "R8") (pin "1") (pinfunction "1_1") (pintype "passive"))
      (node (ref "U4") (pin "18") (pinfunction "2Q_18") (pintype "passive"))
    )
    (net (code "108") (name "Net-(U4-3Q)") (class "Default")
      (node (ref "R12") (pin "1") (pinfunction "1_1") (pintype "passive"))
      (node (ref "U4") (pin "17") (pinfunction "3Q_17") (pintype "passive"))
    )
    (net (code "109") (name "Net-(U4-4Q)") (class "Default")
      (node (ref "R16") (pin "1") (pinfunction "1_1") (pintype "passive"))
      (node (ref "U4") (pin "16") (pinfunction "4Q_16") (pintype "passive"))
    )
    (net (code "110") (name "Net-(U4-5Q)") (class "Default")
      (node (ref "R20") (pin "1") (pinfunction "1_1") (pintype "passive"))
      (node (ref "U4") (pin "15") (pinfunction "5Q_15") (pintype "passive"))
    )
    (net (code "111") (name "Net-(U4-6Q)") (class "Default")
      (node (ref "R24") (pin "1") (pinfunction "1_1") (pintype "passive"))
      (node (ref "U4") (pin "14") (pinfunction "6Q_14") (pintype "passive"))
    )
    (net (code "112") (name "Net-(U4-7Q)") (class "Default")
      (node (ref "R28") (pin "1") (pinfunction "1_1") (pintype "passive"))
      (node (ref "U4") (pin "13") (pinfunction "7Q_13") (pintype "passive"))
    )
    (net (code "113") (name "Net-(U4-8Q)") (class "Default")
      (node (ref "R32") (pin "1") (pinfunction "1_1") (pintype "passive"))
      (node (ref "U4") (pin "12") (pinfunction "8Q_12") (pintype "passive"))
    )
    (net (code "114") (name "Net-(U5-1Q)") (class "Default")
      (node (ref "R33") (pin "1") (pinfunction "1_1") (pintype "passive"))
      (node (ref "U5") (pin "19") (pinfunction "1Q_19") (pintype "passive"))
    )
    (net (code "115") (name "Net-(U5-2Q)") (class "Default")
      (node (ref "R37") (pin "1") (pinfunction "1_1") (pintype "passive"))
      (node (ref "U5") (pin "18") (pinfunction "2Q_18") (pintype "passive"))
    )
    (net (code "116") (name "Net-(U5-3Q)") (class "Default")
      (node (ref "R41") (pin "1") (pinfunction "1_1") (pintype "passive"))
      (node (ref "U5") (pin "17") (pinfunction "3Q_17") (pintype "passive"))
    )
    (net (code "117") (name "Net-(U5-4Q)") (class "Default")
      (node (ref "R45") (pin "1") (pinfunction "1_1") (pintype "passive"))
      (node (ref "U5") (pin "16") (pinfunction "4Q_16") (pintype "passive"))
    )
    (net (code "118") (name "Net-(U5-5Q)") (class "Default")
      (node (ref "R49") (pin "1") (pinfunction "1_1") (pintype "passive"))
      (node (ref "U5") (pin "15") (pinfunction "5Q_15") (pintype "passive"))
    )
    (net (code "119") (name "Net-(U5-6Q)") (class "Default")
      (node (ref "R53") (pin "1") (pinfunction "1_1") (pintype "passive"))
      (node (ref "U5") (pin "14") (pinfunction "6Q_14") (pintype "passive"))
    )
    (net (code "120") (name "Net-(U5-7Q)") (class "Default")
      (node (ref "R57") (pin "1") (pinfunction "1_1") (pintype "passive"))
      (node (ref "U5") (pin "13") (pinfunction "7Q_13") (pintype "passive"))
    )
    (net (code "121") (name "Net-(U5-8Q)") (class "Default")
      (node (ref "R61") (pin "1") (pinfunction "1_1") (pintype "passive"))
      (node (ref "U5") (pin "12") (pinfunction "8Q_12") (pintype "passive"))
    )
    (net (code "122") (name "Net-(U6-1Q)") (class "Default")
      (node (ref "R34") (pin "1") (pinfunction "1_1") (pintype "passive"))
      (node (ref "U6") (pin "19") (pinfunction "1Q_19") (pintype "passive"))
    )
    (net (code "123") (name "Net-(U6-2Q)") (class "Default")
      (node (ref "R38") (pin "1") (pinfunction "1_1") (pintype "passive"))
      (node (ref "U6") (pin "18") (pinfunction "2Q_18") (pintype "passive"))
    )
    (net (code "124") (name "Net-(U6-3Q)") (class "Default")
      (node (ref "R42") (pin "1") (pinfunction "1_1") (pintype "passive"))
      (node (ref "U6") (pin "17") (pinfunction "3Q_17") (pintype "passive"))
    )
    (net (code "125") (name "Net-(U6-4Q)") (class "Default")
      (node (ref "R46") (pin "1") (pinfunction "1_1") (pintype "passive"))
      (node (ref "U6") (pin "16") (pinfunction "4Q_16") (pintype "passive"))
    )
    (net (code "126") (name "Net-(U6-5Q)") (class "Default")
      (node (ref "R50") (pin "1") (pinfunction "1_1") (pintype "passive"))
      (node (ref "U6") (pin "15") (pinfunction "5Q_15") (pintype "passive"))
    )
    (net (code "127") (name "Net-(U6-6Q)") (class "Default")
      (node (ref "R54") (pin "1") (pinfunction "1_1") (pintype "passive"))
      (node (ref "U6") (pin "14") (pinfunction "6Q_14") (pintype "passive"))
    )
    (net (code "128") (name "Net-(U6-7Q)") (class "Default")
      (node (ref "R58") (pin "1") (pinfunction "1_1") (pintype "passive"))
      (node (ref "U6") (pin "13") (pinfunction "7Q_13") (pintype "passive"))
    )
    (net (code "129") (name "Net-(U6-8Q)") (class "Default")
      (node (ref "R62") (pin "1") (pinfunction "1_1") (pintype "passive"))
      (node (ref "U6") (pin "12") (pinfunction "8Q_12") (pintype "passive"))
    )
    (net (code "130") (name "Net-(U7-1Q)") (class "Default")
      (node (ref "R35") (pin "1") (pinfunction "1_1") (pintype "passive"))
      (node (ref "U7") (pin "19") (pinfunction "1Q_19") (pintype "passive"))
    )
    (net (code "131") (name "Net-(U7-2Q)") (class "Default")
      (node (ref "R39") (pin "1") (pinfunction "1_1") (pintype "passive"))
      (node (ref "U7") (pin "18") (pinfunction "2Q_18") (pintype "passive"))
    )
    (net (code "132") (name "Net-(U7-3Q)") (class "Default")
      (node (ref "R43") (pin "1") (pinfunction "1_1") (pintype "passive"))
      (node (ref "U7") (pin "17") (pinfunction "3Q_17") (pintype "passive"))
    )
    (net (code "133") (name "Net-(U7-4Q)") (class "Default")
      (node (ref "R47") (pin "1") (pinfunction "1_1") (pintype "passive"))
      (node (ref "U7") (pin "16") (pinfunction "4Q_16") (pintype "passive"))
    )
    (net (code "134") (name "Net-(U7-5Q)") (class "Default")
      (node (ref "R51") (pin "1") (pinfunction "1_1") (pintype "passive"))
      (node (ref "U7") (pin "15") (pinfunction "5Q_15") (pintype "passive"))
    )
    (net (code "135") (name "Net-(U7-6Q)") (class "Default")
      (node (ref "R55") (pin "1") (pinfunction "1_1") (pintype "passive"))
      (node (ref "U7") (pin "14") (pinfunction "6Q_14") (pintype "passive"))
    )
    (net (code "136") (name "Net-(U7-7Q)") (class "Default")
      (node (ref "R59") (pin "1") (pinfunction "1_1") (pintype "passive"))
      (node (ref "U7") (pin "13") (pinfunction "7Q_13") (pintype "passive"))
    )
    (net (code "137") (name "Net-(U7-8Q)") (class "Default")
      (node (ref "R63") (pin "1") (pinfunction "1_1") (pintype "passive"))
      (node (ref "U7") (pin "12") (pinfunction "8Q_12") (pintype "passive"))
    )
    (net (code "138") (name "Net-(U8-1Q)") (class "Default")
      (node (ref "R36") (pin "1") (pinfunction "1_1") (pintype "passive"))
      (node (ref "U8") (pin "19") (pinfunction "1Q_19") (pintype "passive"))
    )
    (net (code "139") (name "Net-(U8-2Q)") (class "Default")
      (node (ref "R40") (pin "1") (pinfunction "1_1") (pintype "passive"))
      (node (ref "U8") (pin "18") (pinfunction "2Q_18") (pintype "passive"))
    )
    (net (code "140") (name "Net-(U8-3Q)") (class "Default")
      (node (ref "R44") (pin "1") (pinfunction "1_1") (pintype "passive"))
      (node (ref "U8") (pin "17") (pinfunction "3Q_17") (pintype "passive"))
    )
    (net (code "141") (name "Net-(U8-4Q)") (class "Default")
      (node (ref "R48") (pin "1") (pinfunction "1_1") (pintype "passive"))
      (node (ref "U8") (pin "16") (pinfunction "4Q_16") (pintype "passive"))
    )
    (net (code "142") (name "Net-(U8-5Q)") (class "Default")
      (node (ref "R52") (pin "1") (pinfunction "1_1") (pintype "passive"))
      (node (ref "U8") (pin "15") (pinfunction "5Q_15") (pintype "passive"))
    )
    (net (code "143") (name "Net-(U8-6Q)") (class "Default")
      (node (ref "R56") (pin "1") (pinfunction "1_1") (pintype "passive"))
      (node (ref "U8") (pin "14") (pinfunction "6Q_14") (pintype "passive"))
    )
    (net (code "144") (name "Net-(U8-7Q)") (class "Default")
      (node (ref "R60") (pin "1") (pinfunction "1_1") (pintype "passive"))
      (node (ref "U8") (pin "13") (pinfunction "7Q_13") (pintype "passive"))
    )
    (net (code "145") (name "Net-(U8-8Q)") (class "Default")
      (node (ref "R64") (pin "1") (pinfunction "1_1") (pintype "passive"))
      (node (ref "U8") (pin "12") (pinfunction "8Q_12") (pintype "passive"))
    )
    (net (code "146") (name "VCC") (class "Default")
      (node (ref "C1") (pin "2") (pinfunction "2_2") (pintype "passive"))
      (node (ref "C2") (pin "2") (pinfunction "2_2") (pintype "passive"))
      (node (ref "C3") (pin "2") (pinfunction "2_2") (pintype "passive"))
      (node (ref "C4") (pin "2") (pinfunction "2_2") (pintype "passive"))
      (node (ref "C5") (pin "2") (pinfunction "2_2") (pintype "passive"))
      (node (ref "C6") (pin "2") (pinfunction "2_2") (pintype "passive"))
      (node (ref "C7") (pin "2") (pinfunction "2_2") (pintype "passive"))
      (node (ref "C8") (pin "2") (pinfunction "2_2") (pintype "passive"))
      (node (ref "U1") (pin "20") (pinfunction "Vcc_20") (pintype "passive"))
      (node (ref "U2") (pin "20") (pinfunction "Vcc_20") (pintype "passive"))
      (node (ref "U3") (pin "20") (pinfunction "Vcc_20") (pintype "passive"))
      (node (ref "U4") (pin "20") (pinfunction "Vcc_20") (pintype "passive"))
      (node (ref "U5") (pin "20") (pinfunction "Vcc_20") (pintype "passive"))
      (node (ref "U6") (pin "20") (pinfunction "Vcc_20") (pintype "passive"))
      (node (ref "U7") (pin "20") (pinfunction "Vcc_20") (pintype "passive"))
      (node (ref "U8") (pin "20") (pinfunction "Vcc_20") (pintype "passive"))
    )
  )
)
